# TTGO_shield_revE.net
KiCad netlist of a schematic drawn in EAGLE
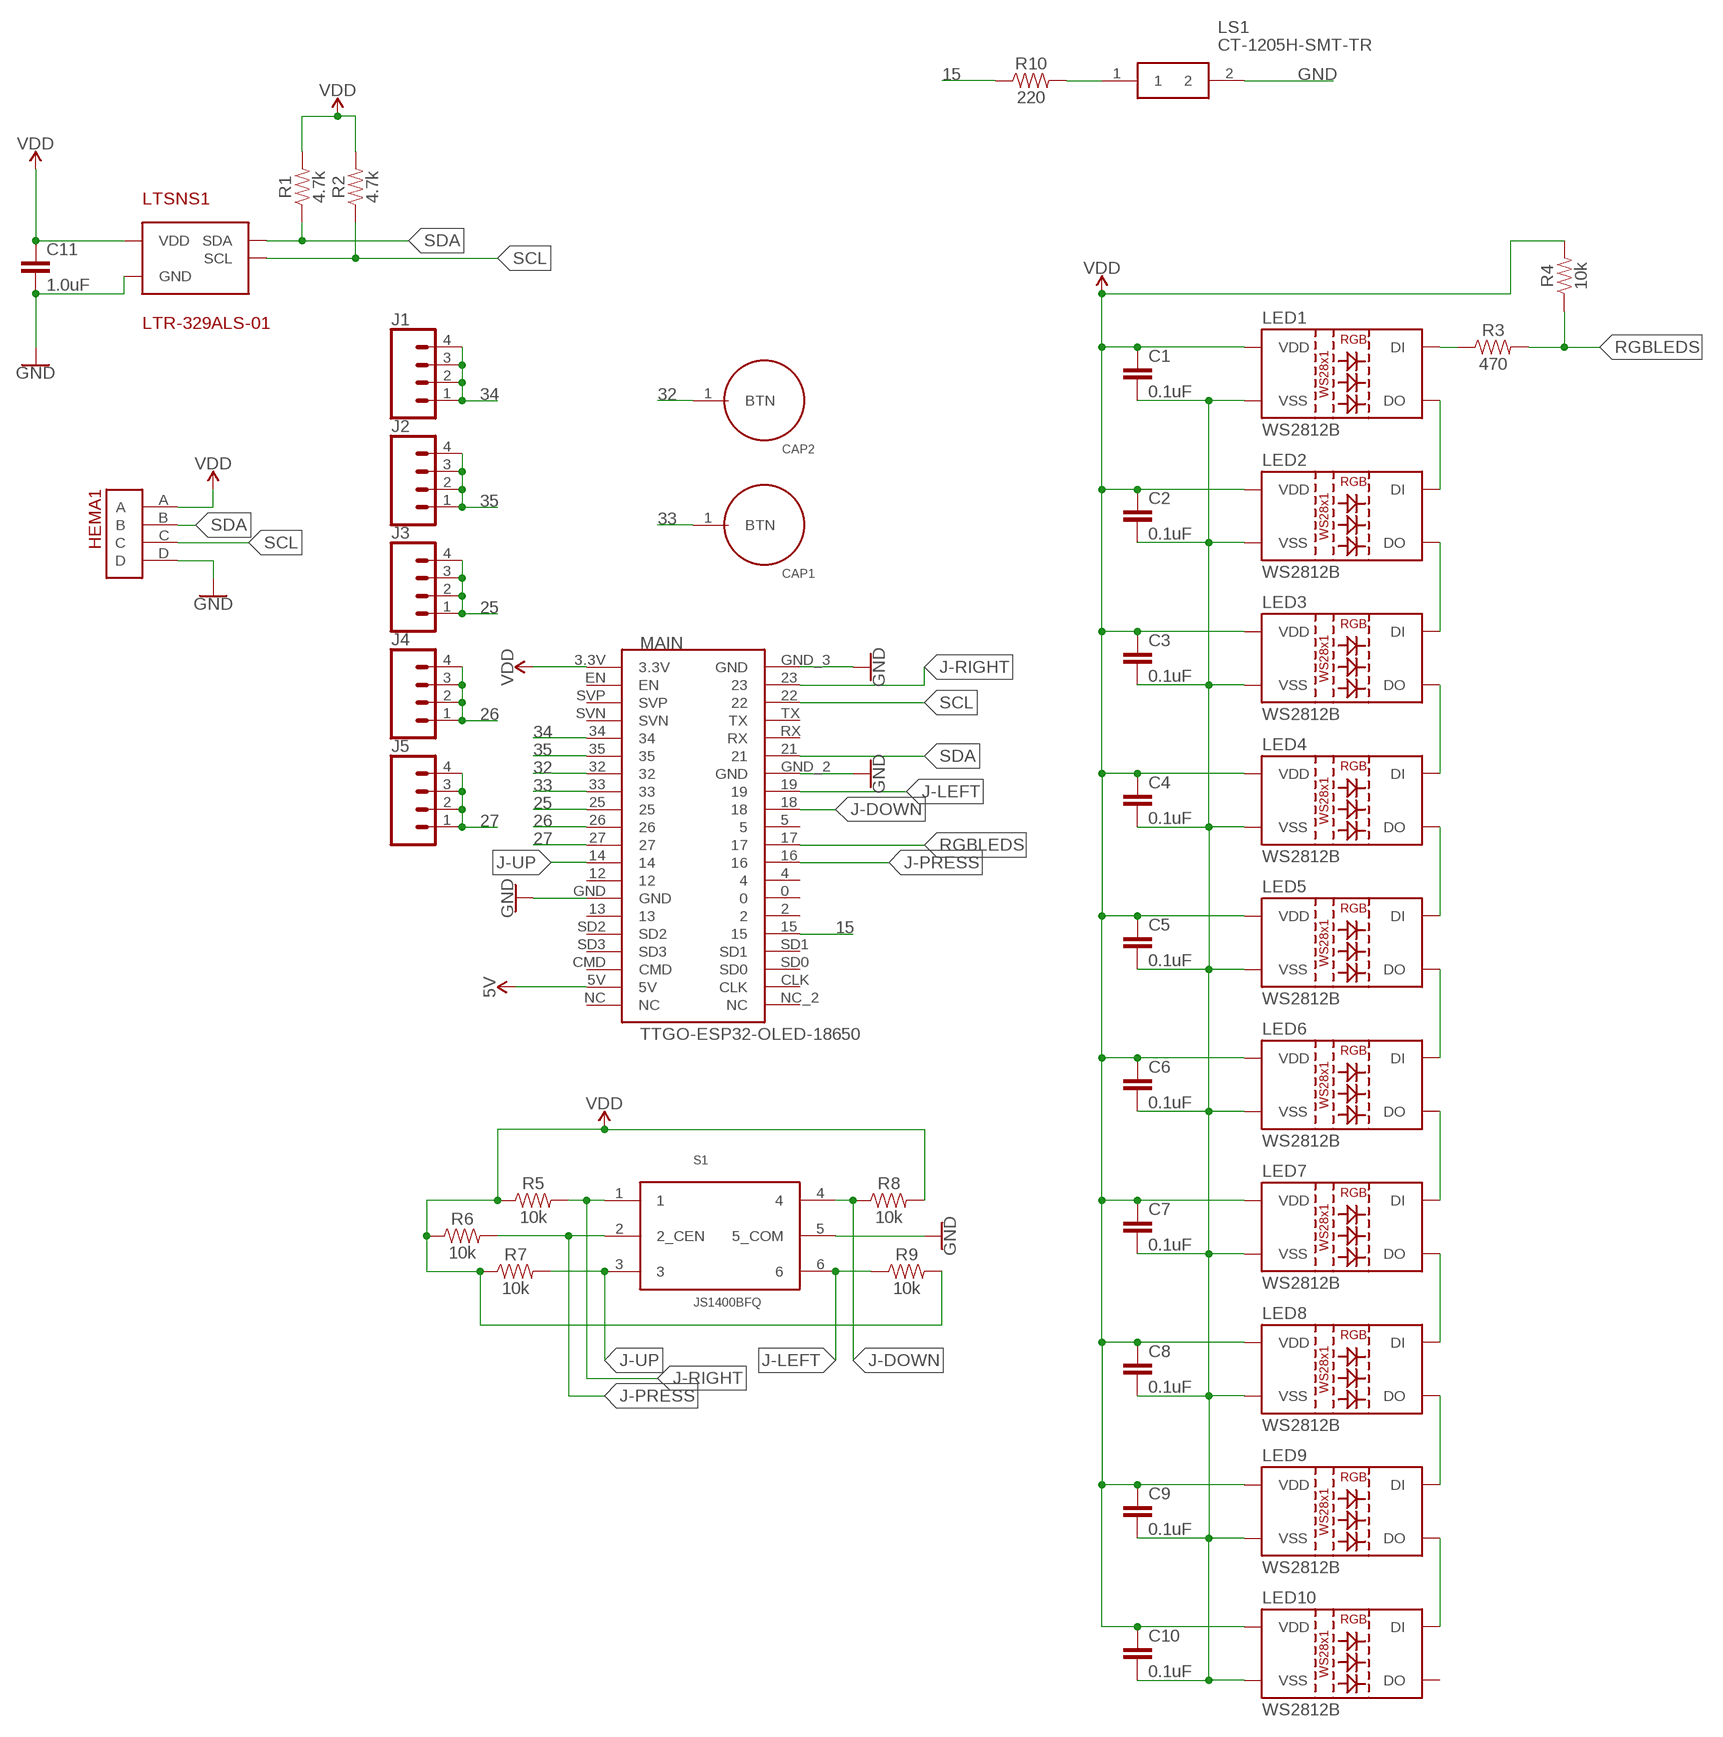
[diagram p0: schematic, sheet 1]

(export (version "E")
  (design (tool "Eeschema 10.0.6"))
  (components
    (comp (ref "C1")
      (value "0.1uF")
      (footprint "eagle-import:0603")
      (libsource (lib "eagle-import") (part "0.1UF-0603-25V-5%"))
    )
    (comp (ref "C2")
      (value "0.1uF")
      (footprint "eagle-import:0603")
      (libsource (lib "eagle-import") (part "0.1UF-0603-25V-5%"))
    )
    (comp (ref "C3")
      (value "0.1uF")
      (footprint "eagle-import:0603")
      (libsource (lib "eagle-import") (part "0.1UF-0603-25V-5%"))
    )
    (comp (ref "C4")
      (value "0.1uF")
      (footprint "eagle-import:0603")
      (libsource (lib "eagle-import") (part "0.1UF-0603-25V-5%"))
    )
    (comp (ref "C5")
      (value "0.1uF")
      (footprint "eagle-import:0603")
      (libsource (lib "eagle-import") (part "0.1UF-0603-25V-5%"))
    )
    (comp (ref "C6")
      (value "0.1uF")
      (footprint "eagle-import:0603")
      (libsource (lib "eagle-import") (part "0.1UF-0603-25V-5%"))
    )
    (comp (ref "C7")
      (value "0.1uF")
      (footprint "eagle-import:0603")
      (libsource (lib "eagle-import") (part "0.1UF-0603-25V-5%"))
    )
    (comp (ref "C8")
      (value "0.1uF")
      (footprint "eagle-import:0603")
      (libsource (lib "eagle-import") (part "0.1UF-0603-25V-5%"))
    )
    (comp (ref "C9")
      (value "0.1uF")
      (footprint "eagle-import:0603")
      (libsource (lib "eagle-import") (part "0.1UF-0603-25V-5%"))
    )
    (comp (ref "C10")
      (value "0.1uF")
      (footprint "eagle-import:0603")
      (libsource (lib "eagle-import") (part "0.1UF-0603-25V-5%"))
    )
    (comp (ref "C11")
      (value "1.0uF")
      (footprint "eagle-import:0805")
      (libsource (lib "eagle-import") (part "1.0UF-0805-25V-10%"))
    )
    (comp (ref "CAP1")
      (value "CAPSENSE_BUTTON")
      (footprint "eagle-import:CAPSENSE_BUTTON")
      (libsource (lib "eagle-import") (part "CAPSENSE_BUTTON"))
    )
    (comp (ref "CAP2")
      (value "CAPSENSE_BUTTON")
      (footprint "eagle-import:CAPSENSE_BUTTON")
      (libsource (lib "eagle-import") (part "CAPSENSE_BUTTON"))
    )
    (comp (ref "HEMA1")
      (value "10120045-400LF")
      (footprint "eagle-import:10120045-400LF")
      (libsource (lib "eagle-import") (part "10120045-400LF"))
    )
    (comp (ref "J1")
      (value "CONN_04LONGPADS")
      (footprint "eagle-import:1X04_LONGPADS")
      (libsource (lib "eagle-import") (part "CONN_04LONGPADS"))
    )
    (comp (ref "J2")
      (value "CONN_04LONGPADS")
      (footprint "eagle-import:1X04_LONGPADS")
      (libsource (lib "eagle-import") (part "CONN_04LONGPADS"))
    )
    (comp (ref "J3")
      (value "CONN_04LONGPADS")
      (footprint "eagle-import:1X04_LONGPADS")
      (libsource (lib "eagle-import") (part "CONN_04LONGPADS"))
    )
    (comp (ref "J4")
      (value "CONN_04LONGPADS")
      (footprint "eagle-import:1X04_LONGPADS")
      (libsource (lib "eagle-import") (part "CONN_04LONGPADS"))
    )
    (comp (ref "J5")
      (value "CONN_04LONGPADS")
      (footprint "eagle-import:1X04_LONGPADS")
      (libsource (lib "eagle-import") (part "CONN_04LONGPADS"))
    )
    (comp (ref "LED1")
      (value "WS2812B")
      (footprint "eagle-import:WS2812B")
      (libsource (lib "eagle-import") (part "WS2812B"))
    )
    (comp (ref "LED2")
      (value "WS2812B")
      (footprint "eagle-import:WS2812B")
      (libsource (lib "eagle-import") (part "WS2812B"))
    )
    (comp (ref "LED3")
      (value "WS2812B")
      (footprint "eagle-import:WS2812B")
      (libsource (lib "eagle-import") (part "WS2812B"))
    )
    (comp (ref "LED4")
      (value "WS2812B")
      (footprint "eagle-import:WS2812B")
      (libsource (lib "eagle-import") (part "WS2812B"))
    )
    (comp (ref "LED5")
      (value "WS2812B")
      (footprint "eagle-import:WS2812B")
      (libsource (lib "eagle-import") (part "WS2812B"))
    )
    (comp (ref "LED6")
      (value "WS2812B")
      (footprint "eagle-import:WS2812B")
      (libsource (lib "eagle-import") (part "WS2812B"))
    )
    (comp (ref "LED7")
      (value "WS2812B")
      (footprint "eagle-import:WS2812B")
      (libsource (lib "eagle-import") (part "WS2812B"))
    )
    (comp (ref "LED8")
      (value "WS2812B")
      (footprint "eagle-import:WS2812B")
      (libsource (lib "eagle-import") (part "WS2812B"))
    )
    (comp (ref "LED9")
      (value "WS2812B")
      (footprint "eagle-import:WS2812B")
      (libsource (lib "eagle-import") (part "WS2812B"))
    )
    (comp (ref "LED10")
      (value "WS2812B")
      (footprint "eagle-import:WS2812B")
      (libsource (lib "eagle-import") (part "WS2812B"))
    )
    (comp (ref "LS1")
      (value "CT-1205H-SMT-TR")
      (footprint "eagle-import:CT1205HSMTTR")
      (libsource (lib "eagle-import") (part "CT-1205H-SMT-TR"))
    )
    (comp (ref "LTSNS1")
      (value "LTR-329ALS-01")
      (footprint "eagle-import:CHIPLED-4")
      (libsource (lib "eagle-import") (part "LTR-329ALS-01"))
    )
    (comp (ref "MAIN")
      (value "TTGO-ESP32-OLED-18650")
      (footprint "eagle-import:TTGO-ESP32-OLED-18650")
      (libsource (lib "eagle-import") (part "TTGO-ESP32-OLED-18650"))
    )
    (comp (ref "R1")
      (value "4.7k")
      (footprint "eagle-import:0603")
      (libsource (lib "eagle-import") (part "4.7KOHM-0603-1/10W-1%"))
    )
    (comp (ref "R2")
      (value "4.7k")
      (footprint "eagle-import:0603")
      (libsource (lib "eagle-import") (part "4.7KOHM-0603-1/10W-1%"))
    )
    (comp (ref "R3")
      (value "470")
      (footprint "eagle-import:0603")
      (libsource (lib "eagle-import") (part "470OHM-0603-1/10W-1%"))
    )
    (comp (ref "R4")
      (value "10k")
      (footprint "eagle-import:0603")
      (libsource (lib "eagle-import") (part "10KOHM-0603-1/10W-1%"))
    )
    (comp (ref "R5")
      (value "10k")
      (footprint "eagle-import:0603")
      (libsource (lib "eagle-import") (part "10KOHM-0603-1/10W-1%"))
    )
    (comp (ref "R6")
      (value "10k")
      (footprint "eagle-import:0603")
      (libsource (lib "eagle-import") (part "10KOHM-0603-1/10W-1%"))
    )
    (comp (ref "R7")
      (value "10k")
      (footprint "eagle-import:0603")
      (libsource (lib "eagle-import") (part "10KOHM-0603-1/10W-1%"))
    )
    (comp (ref "R8")
      (value "10k")
      (footprint "eagle-import:0603")
      (libsource (lib "eagle-import") (part "10KOHM-0603-1/10W-1%"))
    )
    (comp (ref "R9")
      (value "10k")
      (footprint "eagle-import:0603")
      (libsource (lib "eagle-import") (part "10KOHM-0603-1/10W-1%"))
    )
    (comp (ref "R10")
      (value "220")
      (footprint "eagle-import:0603")
      (libsource (lib "eagle-import") (part "470OHM-0603-1/10W-1%"))
    )
    (comp (ref "S1")
      (value "JS1400BFQ")
      (footprint "eagle-import:JS1400BFQ")
      (libsource (lib "eagle-import") (part "JS1400BFQ"))
    )
  )
  (nets
    (net (code "1") (name "/15") (class "Default")
      (node (ref "MAIN") (pin "15") (pinfunction "15_15") (pintype "bidirectional"))
      (node (ref "R10") (pin "1") (pinfunction "1_1") (pintype "passive"))
    )
    (net (code "2") (name "/25") (class "Default")
      (node (ref "J3") (pin "1") (pinfunction "1_1") (pintype "passive"))
      (node (ref "J3") (pin "2") (pinfunction "2_2") (pintype "passive"))
      (node (ref "J3") (pin "3") (pinfunction "3_3") (pintype "passive"))
      (node (ref "J3") (pin "4") (pinfunction "4_4") (pintype "passive"))
      (node (ref "MAIN") (pin "25") (pinfunction "25_25") (pintype "bidirectional"))
    )
    (net (code "3") (name "/26") (class "Default")
      (node (ref "J4") (pin "1") (pinfunction "1_1") (pintype "passive"))
      (node (ref "J4") (pin "2") (pinfunction "2_2") (pintype "passive"))
      (node (ref "J4") (pin "3") (pinfunction "3_3") (pintype "passive"))
      (node (ref "J4") (pin "4") (pinfunction "4_4") (pintype "passive"))
      (node (ref "MAIN") (pin "26") (pinfunction "26_26") (pintype "bidirectional"))
    )
    (net (code "4") (name "/27") (class "Default")
      (node (ref "J5") (pin "1") (pinfunction "1_1") (pintype "passive"))
      (node (ref "J5") (pin "2") (pinfunction "2_2") (pintype "passive"))
      (node (ref "J5") (pin "3") (pinfunction "3_3") (pintype "passive"))
      (node (ref "J5") (pin "4") (pinfunction "4_4") (pintype "passive"))
      (node (ref "MAIN") (pin "27") (pinfunction "27_27") (pintype "bidirectional"))
    )
    (net (code "5") (name "/32") (class "Default")
      (node (ref "CAP2") (pin "1") (pinfunction "BTN_1") (pintype "bidirectional"))
      (node (ref "MAIN") (pin "32") (pinfunction "32_32") (pintype "bidirectional"))
    )
    (net (code "6") (name "/33") (class "Default")
      (node (ref "CAP1") (pin "1") (pinfunction "BTN_1") (pintype "bidirectional"))
      (node (ref "MAIN") (pin "33") (pinfunction "33_33") (pintype "bidirectional"))
    )
    (net (code "7") (name "/34") (class "Default")
      (node (ref "J1") (pin "1") (pinfunction "1_1") (pintype "passive"))
      (node (ref "J1") (pin "2") (pinfunction "2_2") (pintype "passive"))
      (node (ref "J1") (pin "3") (pinfunction "3_3") (pintype "passive"))
      (node (ref "J1") (pin "4") (pinfunction "4_4") (pintype "passive"))
      (node (ref "MAIN") (pin "34") (pinfunction "34_34") (pintype "bidirectional"))
    )
    (net (code "8") (name "/35") (class "Default")
      (node (ref "J2") (pin "1") (pinfunction "1_1") (pintype "passive"))
      (node (ref "J2") (pin "2") (pinfunction "2_2") (pintype "passive"))
      (node (ref "J2") (pin "3") (pinfunction "3_3") (pintype "passive"))
      (node (ref "J2") (pin "4") (pinfunction "4_4") (pintype "passive"))
      (node (ref "MAIN") (pin "35") (pinfunction "35_35") (pintype "bidirectional"))
    )
    (net (code "9") (name "5V") (class "Default")
      (node (ref "MAIN") (pin "5V") (pinfunction "5V_5V") (pintype "bidirectional"))
    )
    (net (code "10") (name "GND") (class "Default")
      (node (ref "C11") (pin "2") (pinfunction "2_2") (pintype "passive"))
      (node (ref "HEMA1") (pin "D") (pinfunction "D_D") (pintype "bidirectional"))
      (node (ref "LS1") (pin "2") (pinfunction "2_2") (pintype "bidirectional"))
      (node (ref "LTSNS1") (pin "2") (pinfunction "GND_2") (pintype "bidirectional"))
      (node (ref "MAIN") (pin "GND") (pinfunction "GND_GND") (pintype "bidirectional"))
      (node (ref "MAIN") (pin "GND_2") (pinfunction "GND_GND_2") (pintype "bidirectional"))
      (node (ref "MAIN") (pin "GND_3") (pinfunction "GND_GND_3") (pintype "bidirectional"))
      (node (ref "S1") (pin "5") (pinfunction "5_COM_5") (pintype "bidirectional"))
    )
    (net (code "11") (name "J-DOWN") (class "Default")
      (node (ref "MAIN") (pin "18") (pinfunction "18_18") (pintype "bidirectional"))
      (node (ref "R8") (pin "1") (pinfunction "1_1") (pintype "passive"))
      (node (ref "S1") (pin "4") (pinfunction "4_4") (pintype "bidirectional"))
    )
    (net (code "12") (name "J-LEFT") (class "Default")
      (node (ref "MAIN") (pin "19") (pinfunction "19_19") (pintype "bidirectional"))
      (node (ref "R9") (pin "1") (pinfunction "1_1") (pintype "passive"))
      (node (ref "S1") (pin "6") (pinfunction "6_6") (pintype "bidirectional"))
    )
    (net (code "13") (name "J-PRESS") (class "Default")
      (node (ref "MAIN") (pin "16") (pinfunction "16_16") (pintype "bidirectional"))
      (node (ref "R6") (pin "2") (pinfunction "2_2") (pintype "passive"))
      (node (ref "S1") (pin "2") (pinfunction "2_CEN_2") (pintype "bidirectional"))
    )
    (net (code "14") (name "J-RIGHT") (class "Default")
      (node (ref "MAIN") (pin "23") (pinfunction "23_23") (pintype "bidirectional"))
      (node (ref "R5") (pin "2") (pinfunction "2_2") (pintype "passive"))
      (node (ref "S1") (pin "1") (pinfunction "1_1") (pintype "bidirectional"))
    )
    (net (code "15") (name "J-UP") (class "Default")
      (node (ref "MAIN") (pin "14") (pinfunction "14_14") (pintype "bidirectional"))
      (node (ref "R7") (pin "2") (pinfunction "2_2") (pintype "passive"))
      (node (ref "S1") (pin "3") (pinfunction "3_3") (pintype "bidirectional"))
    )
    (net (code "16") (name "Net-(LED1-DI)") (class "Default")
      (node (ref "LED1") (pin "4") (pinfunction "DI_4") (pintype "bidirectional"))
      (node (ref "R3") (pin "1") (pinfunction "1_1") (pintype "passive"))
    )
    (net (code "17") (name "Net-(LED1-DO)") (class "Default")
      (node (ref "LED1") (pin "2") (pinfunction "DO_2") (pintype "bidirectional"))
      (node (ref "LED2") (pin "4") (pinfunction "DI_4") (pintype "bidirectional"))
    )
    (net (code "18") (name "Net-(LED1-VSS)") (class "Default")
      (node (ref "C1") (pin "2") (pinfunction "2_2") (pintype "passive"))
      (node (ref "C10") (pin "2") (pinfunction "2_2") (pintype "passive"))
      (node (ref "C2") (pin "2") (pinfunction "2_2") (pintype "passive"))
      (node (ref "C3") (pin "2") (pinfunction "2_2") (pintype "passive"))
      (node (ref "C4") (pin "2") (pinfunction "2_2") (pintype "passive"))
      (node (ref "C5") (pin "2") (pinfunction "2_2") (pintype "passive"))
      (node (ref "C6") (pin "2") (pinfunction "2_2") (pintype "passive"))
      (node (ref "C7") (pin "2") (pinfunction "2_2") (pintype "passive"))
      (node (ref "C8") (pin "2") (pinfunction "2_2") (pintype "passive"))
      (node (ref "C9") (pin "2") (pinfunction "2_2") (pintype "passive"))
      (node (ref "LED1") (pin "3") (pinfunction "VSS_3") (pintype "bidirectional"))
      (node (ref "LED10") (pin "3") (pinfunction "VSS_3") (pintype "bidirectional"))
      (node (ref "LED2") (pin "3") (pinfunction "VSS_3") (pintype "bidirectional"))
      (node (ref "LED3") (pin "3") (pinfunction "VSS_3") (pintype "bidirectional"))
      (node (ref "LED4") (pin "3") (pinfunction "VSS_3") (pintype "bidirectional"))
      (node (ref "LED5") (pin "3") (pinfunction "VSS_3") (pintype "bidirectional"))
      (node (ref "LED6") (pin "3") (pinfunction "VSS_3") (pintype "bidirectional"))
      (node (ref "LED7") (pin "3") (pinfunction "VSS_3") (pintype "bidirectional"))
      (node (ref "LED8") (pin "3") (pinfunction "VSS_3") (pintype "bidirectional"))
      (node (ref "LED9") (pin "3") (pinfunction "VSS_3") (pintype "bidirectional"))
    )
    (net (code "19") (name "Net-(LED2-DO)") (class "Default")
      (node (ref "LED2") (pin "2") (pinfunction "DO_2") (pintype "bidirectional"))
      (node (ref "LED3") (pin "4") (pinfunction "DI_4") (pintype "bidirectional"))
    )
    (net (code "20") (name "Net-(LED3-DO)") (class "Default")
      (node (ref "LED3") (pin "2") (pinfunction "DO_2") (pintype "bidirectional"))
      (node (ref "LED4") (pin "4") (pinfunction "DI_4") (pintype "bidirectional"))
    )
    (net (code "21") (name "Net-(LED4-DO)") (class "Default")
      (node (ref "LED4") (pin "2") (pinfunction "DO_2") (pintype "bidirectional"))
      (node (ref "LED5") (pin "4") (pinfunction "DI_4") (pintype "bidirectional"))
    )
    (net (code "22") (name "Net-(LED5-DO)") (class "Default")
      (node (ref "LED5") (pin "2") (pinfunction "DO_2") (pintype "bidirectional"))
      (node (ref "LED6") (pin "4") (pinfunction "DI_4") (pintype "bidirectional"))
    )
    (net (code "23") (name "Net-(LED6-DO)") (class "Default")
      (node (ref "LED6") (pin "2") (pinfunction "DO_2") (pintype "bidirectional"))
      (node (ref "LED7") (pin "4") (pinfunction "DI_4") (pintype "bidirectional"))
    )
    (net (code "24") (name "Net-(LED7-DO)") (class "Default")
      (node (ref "LED7") (pin "2") (pinfunction "DO_2") (pintype "bidirectional"))
      (node (ref "LED8") (pin "4") (pinfunction "DI_4") (pintype "bidirectional"))
    )
    (net (code "25") (name "Net-(LED8-DO)") (class "Default")
      (node (ref "LED8") (pin "2") (pinfunction "DO_2") (pintype "bidirectional"))
      (node (ref "LED9") (pin "4") (pinfunction "DI_4") (pintype "bidirectional"))
    )
    (net (code "26") (name "Net-(LED10-DI)") (class "Default")
      (node (ref "LED10") (pin "4") (pinfunction "DI_4") (pintype "bidirectional"))
      (node (ref "LED9") (pin "2") (pinfunction "DO_2") (pintype "bidirectional"))
    )
    (net (code "27") (name "Net-(LS1-Pad1)") (class "Default")
      (node (ref "LS1") (pin "1") (pinfunction "1_1") (pintype "bidirectional"))
      (node (ref "R10") (pin "2") (pinfunction "2_2") (pintype "passive"))
    )
    (net (code "28") (name "RGBLEDS") (class "Default")
      (node (ref "MAIN") (pin "17") (pinfunction "17_17") (pintype "bidirectional"))
      (node (ref "R3") (pin "2") (pinfunction "2_2") (pintype "passive"))
      (node (ref "R4") (pin "1") (pinfunction "1_1") (pintype "passive"))
    )
    (net (code "29") (name "SCL") (class "Default")
      (node (ref "HEMA1") (pin "C") (pinfunction "C_C") (pintype "bidirectional"))
      (node (ref "LTSNS1") (pin "4") (pinfunction "SCL_4") (pintype "bidirectional"))
      (node (ref "MAIN") (pin "22") (pinfunction "22_22") (pintype "bidirectional"))
      (node (ref "R2") (pin "1") (pinfunction "1_1") (pintype "passive"))
    )
    (net (code "30") (name "SDA") (class "Default")
      (node (ref "HEMA1") (pin "B") (pinfunction "B_B") (pintype "bidirectional"))
      (node (ref "LTSNS1") (pin "3") (pinfunction "SDA_3") (pintype "bidirectional"))
      (node (ref "MAIN") (pin "21") (pinfunction "21_21") (pintype "bidirectional"))
      (node (ref "R1") (pin "1") (pinfunction "1_1") (pintype "passive"))
    )
    (net (code "31") (name "VDD") (class "Default")
      (node (ref "C1") (pin "1") (pinfunction "1_1") (pintype "passive"))
      (node (ref "C10") (pin "1") (pinfunction "1_1") (pintype "passive"))
      (node (ref "C11") (pin "1") (pinfunction "1_1") (pintype "passive"))
      (node (ref "C2") (pin "1") (pinfunction "1_1") (pintype "passive"))
      (node (ref "C3") (pin "1") (pinfunction "1_1") (pintype "passive"))
      (node (ref "C4") (pin "1") (pinfunction "1_1") (pintype "passive"))
      (node (ref "C5") (pin "1") (pinfunction "1_1") (pintype "passive"))
      (node (ref "C6") (pin "1") (pinfunction "1_1") (pintype "passive"))
      (node (ref "C7") (pin "1") (pinfunction "1_1") (pintype "passive"))
      (node (ref "C8") (pin "1") (pinfunction "1_1") (pintype "passive"))
      (node (ref "C9") (pin "1") (pinfunction "1_1") (pintype "passive"))
      (node (ref "HEMA1") (pin "A") (pinfunction "A_A") (pintype "bidirectional"))
      (node (ref "LED1") (pin "1") (pinfunction "VDD_1") (pintype "bidirectional"))
      (node (ref "LED10") (pin "1") (pinfunction "VDD_1") (pintype "bidirectional"))
      (node (ref "LED2") (pin "1") (pinfunction "VDD_1") (pintype "bidirectional"))
      (node (ref "LED3") (pin "1") (pinfunction "VDD_1") (pintype "bidirectional"))
      (node (ref "LED4") (pin "1") (pinfunction "VDD_1") (pintype "bidirectional"))
      (node (ref "LED5") (pin "1") (pinfunction "VDD_1") (pintype "bidirectional"))
      (node (ref "LED6") (pin "1") (pinfunction "VDD_1") (pintype "bidirectional"))
      (node (ref "LED7") (pin "1") (pinfunction "VDD_1") (pintype "bidirectional"))
      (node (ref "LED8") (pin "1") (pinfunction "VDD_1") (pintype "bidirectional"))
      (node (ref "LED9") (pin "1") (pinfunction "VDD_1") (pintype "bidirectional"))
      (node (ref "LTSNS1") (pin "1") (pinfunction "VDD_1") (pintype "bidirectional"))
      (node (ref "MAIN") (pin "3.3V") (pinfunction "3.3V_3.3V") (pintype "bidirectional"))
      (node (ref "R1") (pin "2") (pinfunction "2_2") (pintype "passive"))
      (node (ref "R2") (pin "2") (pinfunction "2_2") (pintype "passive"))
      (node (ref "R4") (pin "2") (pinfunction "2_2") (pintype "passive"))
      (node (ref "R5") (pin "1") (pinfunction "1_1") (pintype "passive"))
      (node (ref "R6") (pin "1") (pinfunction "1_1") (pintype "passive"))
      (node (ref "R7") (pin "1") (pinfunction "1_1") (pintype "passive"))
      (node (ref "R8") (pin "2") (pinfunction "2_2") (pintype "passive"))
      (node (ref "R9") (pin "2") (pinfunction "2_2") (pintype "passive"))
    )
    (net (code "32") (name "unconnected-(LED10-DO-Pad2)") (class "Default")
      (node (ref "LED10") (pin "2") (pinfunction "DO_2") (pintype "bidirectional"))
    )
    (net (code "33") (name "unconnected-(MAIN-NC-PadNC_2)") (class "Default")
      (node (ref "MAIN") (pin "NC_2") (pinfunction "NC_NC_2") (pintype "bidirectional"))
    )
    (net (code "34") (name "unconnected-(MAIN-Pad0)") (class "Default")
      (node (ref "MAIN") (pin "0") (pinfunction "0_0") (pintype "bidirectional"))
    )
    (net (code "35") (name "unconnected-(MAIN-Pad2)") (class "Default")
      (node (ref "MAIN") (pin "2") (pinfunction "2_2") (pintype "bidirectional"))
    )
    (net (code "36") (name "unconnected-(MAIN-Pad4)") (class "Default")
      (node (ref "MAIN") (pin "4") (pinfunction "4_4") (pintype "bidirectional"))
    )
    (net (code "37") (name "unconnected-(MAIN-Pad5)") (class "Default")
      (node (ref "MAIN") (pin "5") (pinfunction "5_5") (pintype "bidirectional"))
    )
    (net (code "38") (name "unconnected-(MAIN-Pad12)") (class "Default")
      (node (ref "MAIN") (pin "12") (pinfunction "12_12") (pintype "bidirectional"))
    )
    (net (code "39") (name "unconnected-(MAIN-Pad13)") (class "Default")
      (node (ref "MAIN") (pin "13") (pinfunction "13_13") (pintype "bidirectional"))
    )
    (net (code "40") (name "unconnected-(MAIN-PadCLK)") (class "Default")
      (node (ref "MAIN") (pin "CLK") (pinfunction "CLK_CLK") (pintype "bidirectional"))
    )
    (net (code "41") (name "unconnected-(MAIN-PadCMD)") (class "Default")
      (node (ref "MAIN") (pin "CMD") (pinfunction "CMD_CMD") (pintype "bidirectional"))
    )
    (net (code "42") (name "unconnected-(MAIN-PadEN)") (class "Default")
      (node (ref "MAIN") (pin "EN") (pinfunction "EN_EN") (pintype "bidirectional"))
    )
    (net (code "43") (name "unconnected-(MAIN-PadNC)") (class "Default")
      (node (ref "MAIN") (pin "NC") (pinfunction "NC_NC") (pintype "bidirectional"))
    )
    (net (code "44") (name "unconnected-(MAIN-PadRX)") (class "Default")
      (node (ref "MAIN") (pin "RX") (pinfunction "RX_RX") (pintype "bidirectional"))
    )
    (net (code "45") (name "unconnected-(MAIN-PadSD0)") (class "Default")
      (node (ref "MAIN") (pin "SD0") (pinfunction "SD0_SD0") (pintype "bidirectional"))
    )
    (net (code "46") (name "unconnected-(MAIN-PadSD1)") (class "Default")
      (node (ref "MAIN") (pin "SD1") (pinfunction "SD1_SD1") (pintype "bidirectional"))
    )
    (net (code "47") (name "unconnected-(MAIN-PadSD2)") (class "Default")
      (node (ref "MAIN") (pin "SD2") (pinfunction "SD2_SD2") (pintype "bidirectional"))
    )
    (net (code "48") (name "unconnected-(MAIN-PadSD3)") (class "Default")
      (node (ref "MAIN") (pin "SD3") (pinfunction "SD3_SD3") (pintype "bidirectional"))
    )
    (net (code "49") (name "unconnected-(MAIN-PadSVN)") (class "Default")
      (node (ref "MAIN") (pin "SVN") (pinfunction "SVN_SVN") (pintype "bidirectional"))
    )
    (net (code "50") (name "unconnected-(MAIN-PadSVP)") (class "Default")
      (node (ref "MAIN") (pin "SVP") (pinfunction "SVP_SVP") (pintype "bidirectional"))
    )
    (net (code "51") (name "unconnected-(MAIN-PadTX)") (class "Default")
      (node (ref "MAIN") (pin "TX") (pinfunction "TX_TX") (pintype "bidirectional"))
    )
  )
)
